# Sheet2.net
KiCad netlist of a schematic drawn in Altium Designer
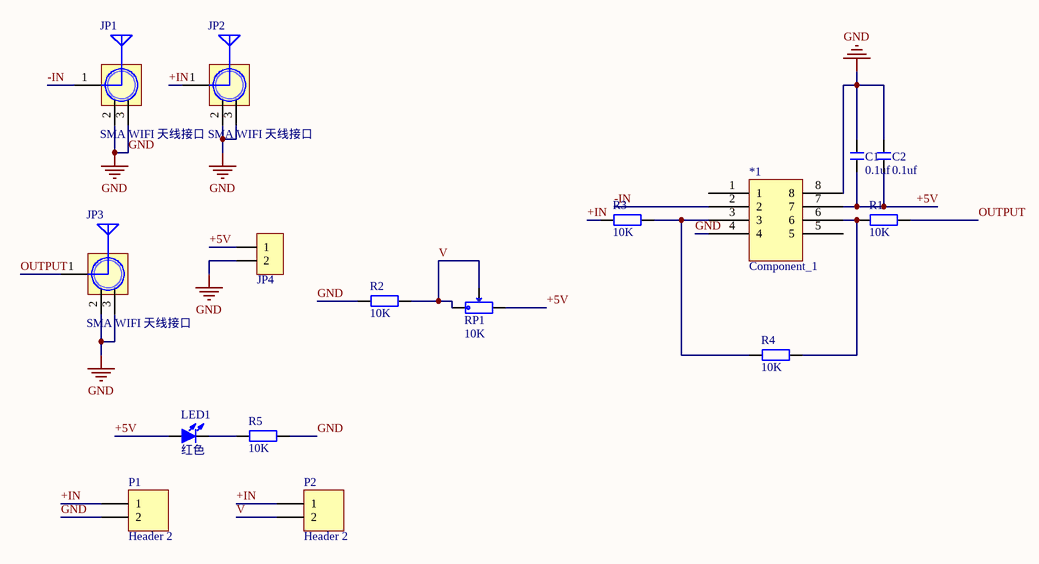
[diagram p0: Sheet2.SchDoc]

(export (version "E")
  (design (tool "Eeschema 10.0.6"))
  (components
    (comp (ref "*1")
      (value "Component_1")
      (footprint "SOP8_N")
      (libsource (lib "Schlib1") (part "Component_1"))
    )
    (comp (ref "C1")
      (value "0.1uf")
      (footprint "C 0603_L")
      (description "贴片电容")
      (libsource (lib "实验室") (part "C"))
    )
    (comp (ref "C2")
      (value "0.1uf")
      (footprint "C 0603_L")
      (description "贴片电容")
      (libsource (lib "实验室") (part "C"))
    )
    (comp (ref "JP1")
      (value "SMA WIFI 天线接口")
      (footprint "SMA-KE")
      (description "SMA-2.4G射频天线接口")
      (fields (field (name "版权归属") "封装库来自淘宝 ID：黄晶宝石"))
      (libsource (lib "1.8 - WiFi天线-SMA射频座") (part "SMA"))
    )
    (comp (ref "JP2")
      (value "SMA WIFI 天线接口")
      (footprint "SMA-KE")
      (description "SMA-2.4G射频天线接口")
      (fields (field (name "版权归属") "封装库来自淘宝 ID：黄晶宝石"))
      (libsource (lib "1.8 - WiFi天线-SMA射频座") (part "SMA"))
    )
    (comp (ref "JP3")
      (value "SMA WIFI 天线接口")
      (footprint "SMA-KE")
      (description "SMA-2.4G射频天线接口")
      (fields (field (name "版权归属") "封装库来自淘宝 ID：黄晶宝石"))
      (libsource (lib "1.8 - WiFi天线-SMA射频座") (part "SMA"))
    )
    (comp (ref "JP4")
      (value "HDR-1X2")
      (footprint "XH2.54-LI-2P")
      (description "2P接插件")
      (libsource (lib "XH2.54") (part "Header 2"))
    )
    (comp (ref "LED1")
      (value "红色")
      (footprint "LED 0805R")
      (description "贴片LED")
      (fields (field (name "版权归属") "源创客"))
      (libsource (lib "实验室") (part "LED-SMD"))
    )
    (comp (ref "P1")
      (value "Header 2")
      (footprint "HDR1X2")
      (description "Header, 2-Pin")
      (fields (field (name "PUBLISHER") "Altium Limited"))
      (libsource (lib "Miscellaneous Connectors") (part "Header 2"))
    )
    (comp (ref "P2")
      (value "Header 2")
      (footprint "HDR1X2")
      (description "Header, 2-Pin")
      (fields (field (name "PUBLISHER") "Altium Limited"))
      (libsource (lib "Miscellaneous Connectors") (part "Header 2"))
    )
    (comp (ref "R1")
      (value "10K")
      (footprint "R 0805_L")
      (description "贴片电阻")
      (fields (field (name "版权归属") "来自淘宝 ID：黄晶宝石"))
      (libsource (lib "实验室") (part "R"))
    )
    (comp (ref "R2")
      (value "10K")
      (footprint "R 0805_L")
      (description "贴片电阻")
      (fields (field (name "版权归属") "来自淘宝 ID：黄晶宝石"))
      (libsource (lib "实验室") (part "R"))
    )
    (comp (ref "R3")
      (value "10K")
      (footprint "R 0805_L")
      (description "贴片电阻")
      (fields (field (name "版权归属") "来自淘宝 ID：黄晶宝石"))
      (libsource (lib "实验室") (part "R"))
    )
    (comp (ref "R4")
      (value "10K")
      (footprint "R 0805_L")
      (description "贴片电阻")
      (fields (field (name "版权归属") "来自淘宝 ID：黄晶宝石"))
      (libsource (lib "实验室") (part "R"))
    )
    (comp (ref "R5")
      (value "10K")
      (footprint "R 0805_L")
      (description "贴片电阻")
      (fields (field (name "版权归属") "来自淘宝 ID：黄晶宝石"))
      (libsource (lib "实验室") (part "R"))
    )
    (comp (ref "RP1")
      (value "10K")
      (footprint "3303W")
      (description "插件单联电位器")
      (libsource (lib "电容-电阻-电感-电位器") (part "RP-ID"))
    )
  )
  (nets
    (net (code "1") (name "/+5V") (class "Default")
      (node (ref "*1") (pin "7") (pinfunction "7_7") (pintype "passive"))
      (node (ref "C1") (pin "1") (pinfunction "1_1") (pintype "passive"))
      (node (ref "C2") (pin "1") (pinfunction "1_1") (pintype "passive"))
      (node (ref "JP4") (pin "1") (pinfunction "1_1") (pintype "passive"))
      (node (ref "LED1") (pin "1") (pinfunction "A_1") (pintype "passive"))
      (node (ref "RP1") (pin "3") (pinfunction "3_3") (pintype "passive"))
    )
    (net (code "2") (name "/+IN") (class "Default")
      (node (ref "JP2") (pin "1") (pinfunction "ANT_1") (pintype "passive"))
      (node (ref "P1") (pin "1") (pinfunction "1_1") (pintype "passive"))
      (node (ref "P2") (pin "1") (pinfunction "1_1") (pintype "passive"))
      (node (ref "R3") (pin "2") (pinfunction "2_2") (pintype "passive"))
    )
    (net (code "3") (name "/-IN") (class "Default")
      (node (ref "*1") (pin "2") (pinfunction "2_2") (pintype "passive"))
      (node (ref "JP1") (pin "1") (pinfunction "ANT_1") (pintype "passive"))
    )
    (net (code "4") (name "/OUTPUT") (class "Default")
      (node (ref "JP3") (pin "1") (pinfunction "ANT_1") (pintype "passive"))
      (node (ref "R1") (pin "2") (pinfunction "2_2") (pintype "passive"))
    )
    (net (code "5") (name "/V") (class "Default")
      (node (ref "P2") (pin "2") (pinfunction "2_2") (pintype "passive"))
      (node (ref "R2") (pin "1") (pinfunction "1_1") (pintype "passive"))
      (node (ref "RP1") (pin "1") (pinfunction "1_1") (pintype "passive"))
      (node (ref "RP1") (pin "2") (pinfunction "2_2") (pintype "passive"))
    )
    (net (code "6") (name "GND") (class "Default")
      (node (ref "*1") (pin "4") (pinfunction "4_4") (pintype "passive"))
      (node (ref "*1") (pin "8") (pinfunction "8_8") (pintype "passive"))
      (node (ref "C1") (pin "2") (pinfunction "2_2") (pintype "passive"))
      (node (ref "C2") (pin "2") (pinfunction "2_2") (pintype "passive"))
      (node (ref "JP1") (pin "2") (pinfunction "GND_2") (pintype "passive"))
      (node (ref "JP1") (pin "3") (pinfunction "GND_3") (pintype "passive"))
      (node (ref "JP2") (pin "2") (pinfunction "GND_2") (pintype "passive"))
      (node (ref "JP2") (pin "3") (pinfunction "GND_3") (pintype "passive"))
      (node (ref "JP3") (pin "2") (pinfunction "GND_2") (pintype "passive"))
      (node (ref "JP3") (pin "3") (pinfunction "GND_3") (pintype "passive"))
      (node (ref "JP4") (pin "2") (pinfunction "2_2") (pintype "passive"))
      (node (ref "P1") (pin "2") (pinfunction "2_2") (pintype "passive"))
      (node (ref "R2") (pin "2") (pinfunction "2_2") (pintype "passive"))
      (node (ref "R5") (pin "2") (pinfunction "2_2") (pintype "passive"))
    )
    (net (code "7") (name "Net-(*1-Pad3)") (class "Default")
      (node (ref "*1") (pin "3") (pinfunction "3_3") (pintype "passive"))
      (node (ref "R3") (pin "1") (pinfunction "1_1") (pintype "passive"))
      (node (ref "R4") (pin "1") (pinfunction "1_1") (pintype "passive"))
    )
    (net (code "8") (name "Net-(*1-Pad6)") (class "Default")
      (node (ref "*1") (pin "6") (pinfunction "6_6") (pintype "passive"))
      (node (ref "R1") (pin "1") (pinfunction "1_1") (pintype "passive"))
      (node (ref "R4") (pin "2") (pinfunction "2_2") (pintype "passive"))
    )
    (net (code "9") (name "Net-(LED1-K)") (class "Default")
      (node (ref "LED1") (pin "2") (pinfunction "K_2") (pintype "passive"))
      (node (ref "R5") (pin "1") (pinfunction "1_1") (pintype "passive"))
    )
    (net (code "10") (name "unconnected-(*1-Pad1)") (class "Default")
      (node (ref "*1") (pin "1") (pinfunction "1_1") (pintype "passive"))
    )
    (net (code "11") (name "unconnected-(*1-Pad5)") (class "Default")
      (node (ref "*1") (pin "5") (pinfunction "5_5") (pintype "passive"))
    )
  )
)
